# Heater.net
KiCad netlist of a schematic drawn in Altium Designer
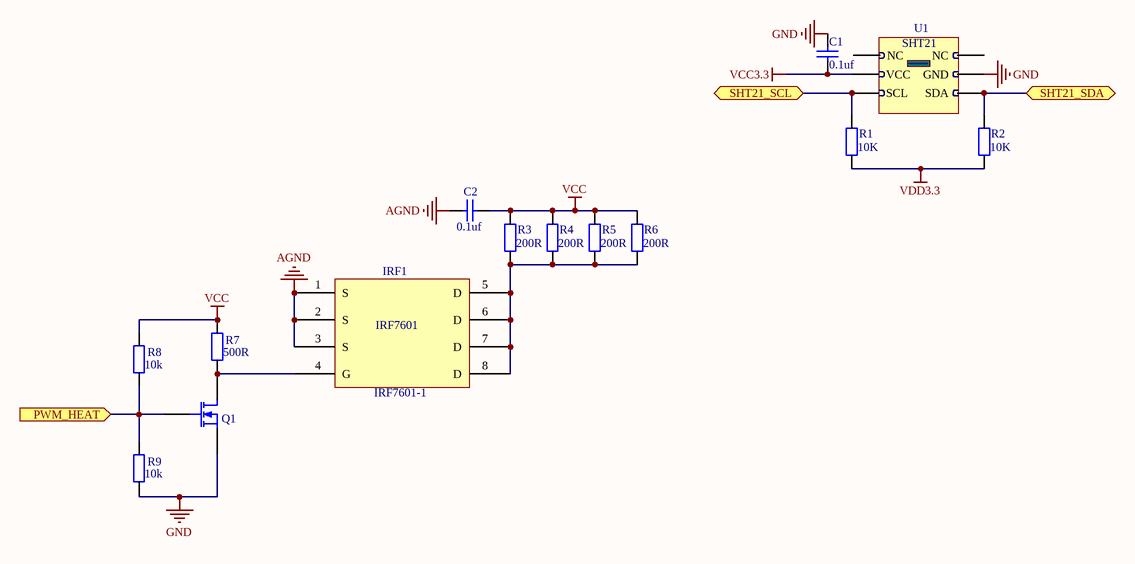
[diagram p0: Heater.SchDoc]

(export (version "E")
  (design (tool "Eeschema 10.0.6"))
  (components
    (comp (ref "C1")
      (value "0.1uf")
      (footprint "0603")
      (fields (field (name "Comment") "Capacitor-0603"))
      (libsource (lib "原理图库") (part "Capacitor-0603"))
    )
    (comp (ref "C2")
      (value "0.1uf")
      (footprint "0603")
      (fields (field (name "Comment") "Capacitor-0603"))
      (libsource (lib "原理图库") (part "Capacitor-0603"))
    )
    (comp (ref "IRF1")
      (value "IRF7601-1")
      (footprint "IRF7601_Micro")
      (description "IRF7601")
      (libsource (lib "*") (part "Component_1"))
    )
    (comp (ref "Q1") (value "MOSFET_N") (footprint "MOSFET_N") (libsource (lib "原理图库") (part "MOSFET_N")))
    (comp (ref "R1")
      (value "10K")
      (footprint "0603")
      (fields (field (name "Comment") "Resistor-0603"))
      (libsource (lib "原理图库") (part "Resistor-0603"))
    )
    (comp (ref "R2")
      (value "10K")
      (footprint "0603")
      (fields (field (name "Comment") "Resistor-0603"))
      (libsource (lib "原理图库") (part "Resistor-0603"))
    )
    (comp (ref "R3")
      (value "200R")
      (footprint "0805")
      (fields (field (name "Comment") "Resistor-0805"))
      (libsource (lib "原理图库") (part "Resistor-0805"))
    )
    (comp (ref "R4")
      (value "200R")
      (footprint "0805")
      (fields (field (name "Comment") "Resistor-0805"))
      (libsource (lib "原理图库") (part "Resistor-0805"))
    )
    (comp (ref "R5")
      (value "200R")
      (footprint "0805")
      (fields (field (name "Comment") "Resistor-0805"))
      (libsource (lib "原理图库") (part "Resistor-0805"))
    )
    (comp (ref "R6")
      (value "200R")
      (footprint "0805")
      (fields (field (name "Comment") "Resistor-0805"))
      (libsource (lib "原理图库") (part "Resistor-0805"))
    )
    (comp (ref "R7")
      (value "500R")
      (footprint "0603")
      (fields (field (name "Comment") "Resistor-0603"))
      (libsource (lib "原理图库") (part "Resistor-0603"))
    )
    (comp (ref "R8")
      (value "10k")
      (footprint "0603")
      (fields (field (name "Comment") "Resistor-0603"))
      (libsource (lib "原理图库") (part "Resistor-0603"))
    )
    (comp (ref "R9")
      (value "10k")
      (footprint "0603")
      (fields (field (name "Comment") "Resistor-0603"))
      (libsource (lib "原理图库") (part "Resistor-0603"))
    )
    (comp (ref "U1")
      (value "SHIT21")
      (footprint "SHT21")
      (fields (field (name "NAME") "SHT21"))
      (libsource (lib "原理图库") (part "SHIT21"))
    )
  )
  (nets
    (net (code "1") (name "/PWM_HEAT") (class "Default")
      (node (ref "Q1") (pin "1") (pinfunction "G_1") (pintype "passive"))
      (node (ref "R8") (pin "1") (pinfunction "1_1") (pintype "passive"))
      (node (ref "R9") (pin "2") (pinfunction "2_2") (pintype "passive"))
    )
    (net (code "2") (name "/SHT21_SCL") (class "Default")
      (node (ref "R1") (pin "2") (pinfunction "2_2") (pintype "passive"))
      (node (ref "U1") (pin "5") (pinfunction "SCL_5") (pintype "passive"))
    )
    (net (code "3") (name "/SHT21_SDA") (class "Default")
      (node (ref "R2") (pin "2") (pinfunction "2_2") (pintype "passive"))
      (node (ref "U1") (pin "6") (pinfunction "SDA_6") (pintype "passive"))
    )
    (net (code "4") (name "AGND") (class "Default")
      (node (ref "C2") (pin "2") (pinfunction "2_2") (pintype "passive"))
      (node (ref "IRF1") (pin "1") (pinfunction "S_1") (pintype "power_in"))
      (node (ref "IRF1") (pin "2") (pinfunction "S_2") (pintype "power_in"))
      (node (ref "IRF1") (pin "3") (pinfunction "S_3") (pintype "power_in"))
    )
    (net (code "5") (name "GND") (class "Default")
      (node (ref "C1") (pin "2") (pinfunction "2_2") (pintype "passive"))
      (node (ref "Q1") (pin "2") (pinfunction "S_2") (pintype "passive"))
      (node (ref "R9") (pin "1") (pinfunction "1_1") (pintype "passive"))
      (node (ref "U1") (pin "4") (pinfunction "GND_4") (pintype "passive"))
    )
    (net (code "6") (name "Net-(IRF1-D-Pad5)") (class "Default")
      (node (ref "IRF1") (pin "5") (pinfunction "D_5") (pintype "power_in"))
      (node (ref "IRF1") (pin "6") (pinfunction "D_6") (pintype "power_in"))
      (node (ref "IRF1") (pin "7") (pinfunction "D_7") (pintype "power_in"))
      (node (ref "IRF1") (pin "8") (pinfunction "D_8") (pintype "power_in"))
      (node (ref "R3") (pin "1") (pinfunction "1_1") (pintype "passive"))
      (node (ref "R4") (pin "1") (pinfunction "1_1") (pintype "passive"))
      (node (ref "R5") (pin "1") (pinfunction "1_1") (pintype "passive"))
      (node (ref "R6") (pin "1") (pinfunction "1_1") (pintype "passive"))
    )
    (net (code "7") (name "Net-(IRF1-G)") (class "Default")
      (node (ref "IRF1") (pin "4") (pinfunction "G_4") (pintype "power_in"))
      (node (ref "Q1") (pin "3") (pinfunction "D_3") (pintype "passive"))
      (node (ref "R7") (pin "1") (pinfunction "1_1") (pintype "passive"))
    )
    (net (code "8") (name "VCC") (class "Default")
      (node (ref "C2") (pin "1") (pinfunction "1_1") (pintype "passive"))
      (node (ref "R3") (pin "2") (pinfunction "2_2") (pintype "passive"))
      (node (ref "R4") (pin "2") (pinfunction "2_2") (pintype "passive"))
      (node (ref "R5") (pin "2") (pinfunction "2_2") (pintype "passive"))
      (node (ref "R6") (pin "2") (pinfunction "2_2") (pintype "passive"))
      (node (ref "R7") (pin "2") (pinfunction "2_2") (pintype "passive"))
      (node (ref "R8") (pin "2") (pinfunction "2_2") (pintype "passive"))
    )
    (net (code "9") (name "VCC3.3") (class "Default")
      (node (ref "C1") (pin "1") (pinfunction "1_1") (pintype "passive"))
      (node (ref "U1") (pin "3") (pinfunction "VCC_3") (pintype "passive"))
    )
    (net (code "10") (name "VDD3.3") (class "Default")
      (node (ref "R1") (pin "1") (pinfunction "1_1") (pintype "passive"))
      (node (ref "R2") (pin "1") (pinfunction "1_1") (pintype "passive"))
    )
    (net (code "11") (name "unconnected-(U1-NC-Pad1)") (class "Default")
      (node (ref "U1") (pin "1") (pinfunction "NC_1") (pintype "passive"))
    )
    (net (code "12") (name "unconnected-(U1-NC-Pad2)") (class "Default")
      (node (ref "U1") (pin "2") (pinfunction "NC_2") (pintype "passive"))
    )
  )
)
